# Wheel_speed_tester_rev1.net
KiCad netlist of a schematic drawn in EAGLE
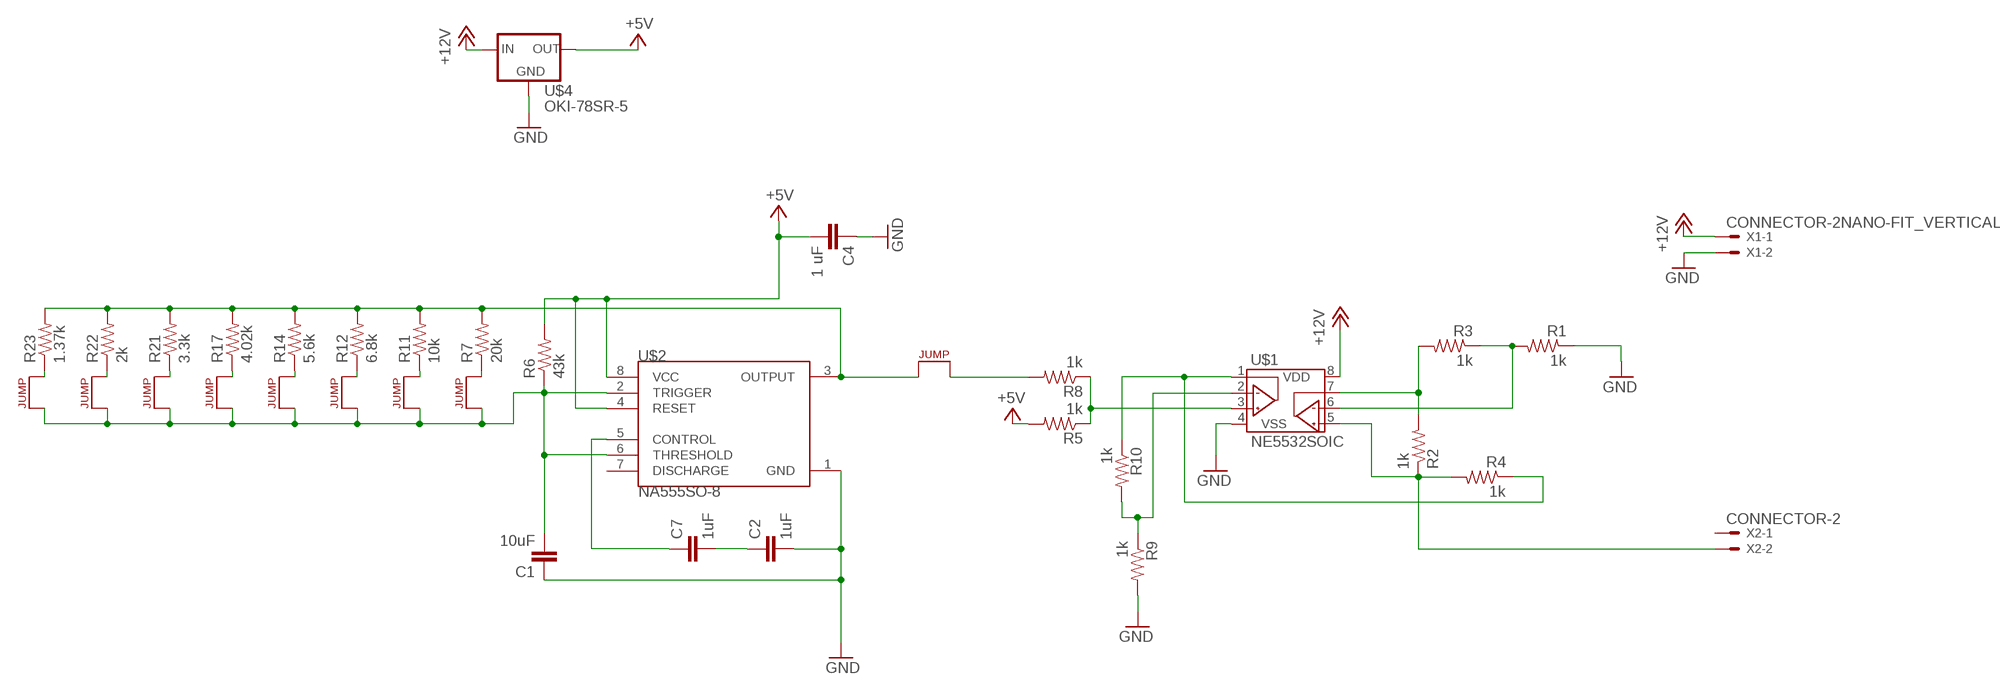
[diagram p0: schematic, sheet 1, part 1 of 2]
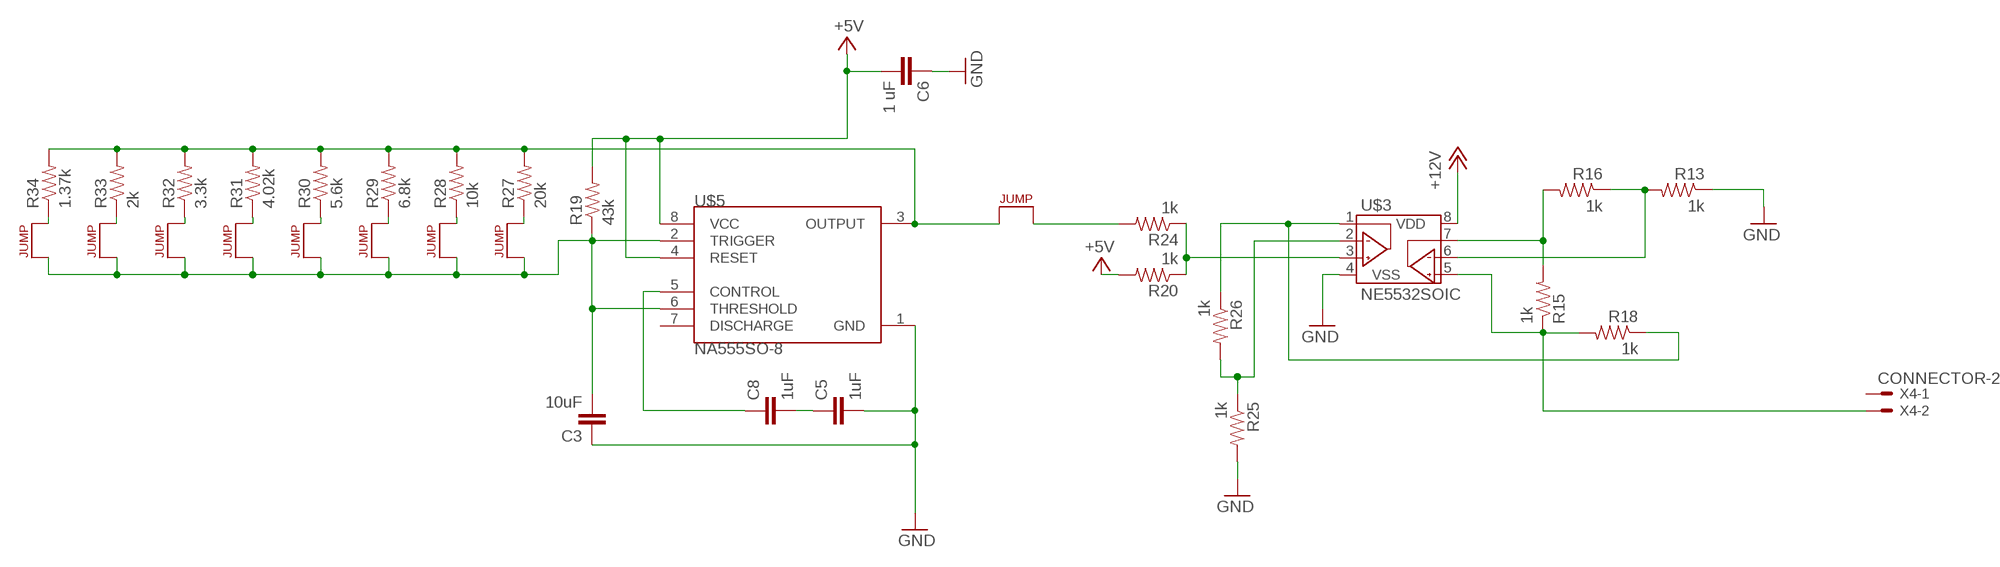
[diagram p1: schematic, sheet 1, part 2 of 2]

(export (version "E")
  (design (tool "Eeschema 10.0.6"))
  (components
    (comp (ref "C1")
      (value "10uF")
      (footprint "eagle-import:0603-CAP")
      (libsource (lib "eagle-import") (part "CAP0603-CAP"))
    )
    (comp (ref "C2")
      (value "1uF")
      (footprint "eagle-import:0603-CAP")
      (libsource (lib "eagle-import") (part "CAP0603-CAP"))
    )
    (comp (ref "C3")
      (value "10uF")
      (footprint "eagle-import:0603-CAP")
      (libsource (lib "eagle-import") (part "CAP0603-CAP"))
    )
    (comp (ref "C4")
      (value "1 uF")
      (footprint "eagle-import:0603-CAP")
      (libsource (lib "eagle-import") (part "CAP0603-CAP"))
    )
    (comp (ref "C5")
      (value "1uF")
      (footprint "eagle-import:0603-CAP")
      (libsource (lib "eagle-import") (part "CAP0603-CAP"))
    )
    (comp (ref "C6")
      (value "1 uF")
      (footprint "eagle-import:0603-CAP")
      (libsource (lib "eagle-import") (part "CAP0603-CAP"))
    )
    (comp (ref "C7")
      (value "1uF")
      (footprint "eagle-import:0603-CAP")
      (libsource (lib "eagle-import") (part "CAP0603-CAP"))
    )
    (comp (ref "C8")
      (value "1uF")
      (footprint "eagle-import:0603-CAP")
      (libsource (lib "eagle-import") (part "CAP0603-CAP"))
    )
    (comp (ref "J1")
      (value "JUMPER.1")
      (footprint "eagle-import:1X02")
      (libsource (lib "eagle-import") (part "JUMPER.1"))
    )
    (comp (ref "J2")
      (value "JUMPER.1")
      (footprint "eagle-import:1X02")
      (libsource (lib "eagle-import") (part "JUMPER.1"))
    )
    (comp (ref "J3")
      (value "JUMPER.1")
      (footprint "eagle-import:1X02")
      (libsource (lib "eagle-import") (part "JUMPER.1"))
    )
    (comp (ref "J4")
      (value "JUMPER.1")
      (footprint "eagle-import:1X02")
      (libsource (lib "eagle-import") (part "JUMPER.1"))
    )
    (comp (ref "J5")
      (value "JUMPER.1")
      (footprint "eagle-import:1X02")
      (libsource (lib "eagle-import") (part "JUMPER.1"))
    )
    (comp (ref "J6")
      (value "JUMPER.1")
      (footprint "eagle-import:1X02")
      (libsource (lib "eagle-import") (part "JUMPER.1"))
    )
    (comp (ref "J7")
      (value "JUMPER.1")
      (footprint "eagle-import:1X02")
      (libsource (lib "eagle-import") (part "JUMPER.1"))
    )
    (comp (ref "J8")
      (value "JUMPER.1")
      (footprint "eagle-import:1X02")
      (libsource (lib "eagle-import") (part "JUMPER.1"))
    )
    (comp (ref "J9")
      (value "JUMPER.1")
      (footprint "eagle-import:1X02")
      (libsource (lib "eagle-import") (part "JUMPER.1"))
    )
    (comp (ref "J10")
      (value "JUMPER.1")
      (footprint "eagle-import:1X02")
      (libsource (lib "eagle-import") (part "JUMPER.1"))
    )
    (comp (ref "J11")
      (value "JUMPER.1")
      (footprint "eagle-import:1X02")
      (libsource (lib "eagle-import") (part "JUMPER.1"))
    )
    (comp (ref "J12")
      (value "JUMPER.1")
      (footprint "eagle-import:1X02")
      (libsource (lib "eagle-import") (part "JUMPER.1"))
    )
    (comp (ref "J13")
      (value "JUMPER.1")
      (footprint "eagle-import:1X02")
      (libsource (lib "eagle-import") (part "JUMPER.1"))
    )
    (comp (ref "J14")
      (value "JUMPER.1")
      (footprint "eagle-import:1X02")
      (libsource (lib "eagle-import") (part "JUMPER.1"))
    )
    (comp (ref "J15")
      (value "JUMPER.1")
      (footprint "eagle-import:1X02")
      (libsource (lib "eagle-import") (part "JUMPER.1"))
    )
    (comp (ref "J16")
      (value "JUMPER.1")
      (footprint "eagle-import:1X02")
      (libsource (lib "eagle-import") (part "JUMPER.1"))
    )
    (comp (ref "J17")
      (value "JUMPER.1")
      (footprint "eagle-import:1X02")
      (libsource (lib "eagle-import") (part "JUMPER.1"))
    )
    (comp (ref "J18")
      (value "JUMPER.1")
      (footprint "eagle-import:1X02")
      (libsource (lib "eagle-import") (part "JUMPER.1"))
    )
    (comp (ref "R1")
      (value "1k")
      (footprint "eagle-import:0603-RES")
      (libsource (lib "eagle-import") (part "RESISTOR0603"))
    )
    (comp (ref "R2")
      (value "1k")
      (footprint "eagle-import:0603-RES")
      (libsource (lib "eagle-import") (part "RESISTOR0603"))
    )
    (comp (ref "R3")
      (value "1k")
      (footprint "eagle-import:0603-RES")
      (libsource (lib "eagle-import") (part "RESISTOR0603"))
    )
    (comp (ref "R4")
      (value "1k")
      (footprint "eagle-import:0603-RES")
      (libsource (lib "eagle-import") (part "RESISTOR0603"))
    )
    (comp (ref "R5")
      (value "1k")
      (footprint "eagle-import:0603-RES")
      (libsource (lib "eagle-import") (part "RESISTOR0603"))
    )
    (comp (ref "R6")
      (value "43k")
      (footprint "eagle-import:0603-RES")
      (libsource (lib "eagle-import") (part "RESISTOR0603"))
    )
    (comp (ref "R7")
      (value "20k")
      (footprint "eagle-import:0603-RES")
      (libsource (lib "eagle-import") (part "RESISTOR0603"))
    )
    (comp (ref "R8")
      (value "1k")
      (footprint "eagle-import:0603-RES")
      (libsource (lib "eagle-import") (part "RESISTOR0603"))
    )
    (comp (ref "R9")
      (value "1k")
      (footprint "eagle-import:0603-RES")
      (libsource (lib "eagle-import") (part "RESISTOR0603"))
    )
    (comp (ref "R10")
      (value "1k")
      (footprint "eagle-import:0603-RES")
      (libsource (lib "eagle-import") (part "RESISTOR0603"))
    )
    (comp (ref "R11")
      (value "10k")
      (footprint "eagle-import:0603-RES")
      (libsource (lib "eagle-import") (part "RESISTOR0603"))
    )
    (comp (ref "R12")
      (value "6.8k")
      (footprint "eagle-import:0603-RES")
      (libsource (lib "eagle-import") (part "RESISTOR0603"))
    )
    (comp (ref "R13")
      (value "1k")
      (footprint "eagle-import:0603-RES")
      (libsource (lib "eagle-import") (part "RESISTOR0603"))
    )
    (comp (ref "R14")
      (value "5.6k")
      (footprint "eagle-import:0603-RES")
      (libsource (lib "eagle-import") (part "RESISTOR0603"))
    )
    (comp (ref "R15")
      (value "1k")
      (footprint "eagle-import:0603-RES")
      (libsource (lib "eagle-import") (part "RESISTOR0603"))
    )
    (comp (ref "R16")
      (value "1k")
      (footprint "eagle-import:0603-RES")
      (libsource (lib "eagle-import") (part "RESISTOR0603"))
    )
    (comp (ref "R17")
      (value "4.02k")
      (footprint "eagle-import:0603-RES")
      (libsource (lib "eagle-import") (part "RESISTOR0603"))
    )
    (comp (ref "R18")
      (value "1k")
      (footprint "eagle-import:0603-RES")
      (libsource (lib "eagle-import") (part "RESISTOR0603"))
    )
    (comp (ref "R19")
      (value "43k")
      (footprint "eagle-import:0603-RES")
      (libsource (lib "eagle-import") (part "RESISTOR0603"))
    )
    (comp (ref "R20")
      (value "1k")
      (footprint "eagle-import:0603-RES")
      (libsource (lib "eagle-import") (part "RESISTOR0603"))
    )
    (comp (ref "R21")
      (value "3.3k")
      (footprint "eagle-import:0603-RES")
      (libsource (lib "eagle-import") (part "RESISTOR0603"))
    )
    (comp (ref "R22")
      (value "2k")
      (footprint "eagle-import:0603-RES")
      (libsource (lib "eagle-import") (part "RESISTOR0603"))
    )
    (comp (ref "R23")
      (value "1.37k")
      (footprint "eagle-import:0603-RES")
      (libsource (lib "eagle-import") (part "RESISTOR0603"))
    )
    (comp (ref "R24")
      (value "1k")
      (footprint "eagle-import:0603-RES")
      (libsource (lib "eagle-import") (part "RESISTOR0603"))
    )
    (comp (ref "R25")
      (value "1k")
      (footprint "eagle-import:0603-RES")
      (libsource (lib "eagle-import") (part "RESISTOR0603"))
    )
    (comp (ref "R26")
      (value "1k")
      (footprint "eagle-import:0603-RES")
      (libsource (lib "eagle-import") (part "RESISTOR0603"))
    )
    (comp (ref "R27")
      (value "20k")
      (footprint "eagle-import:0603-RES")
      (libsource (lib "eagle-import") (part "RESISTOR0603"))
    )
    (comp (ref "R28")
      (value "10k")
      (footprint "eagle-import:0603-RES")
      (libsource (lib "eagle-import") (part "RESISTOR0603"))
    )
    (comp (ref "R29")
      (value "6.8k")
      (footprint "eagle-import:0603-RES")
      (libsource (lib "eagle-import") (part "RESISTOR0603"))
    )
    (comp (ref "R30")
      (value "5.6k")
      (footprint "eagle-import:0603-RES")
      (libsource (lib "eagle-import") (part "RESISTOR0603"))
    )
    (comp (ref "R31")
      (value "4.02k")
      (footprint "eagle-import:0603-RES")
      (libsource (lib "eagle-import") (part "RESISTOR0603"))
    )
    (comp (ref "R32")
      (value "3.3k")
      (footprint "eagle-import:0603-RES")
      (libsource (lib "eagle-import") (part "RESISTOR0603"))
    )
    (comp (ref "R33")
      (value "2k")
      (footprint "eagle-import:0603-RES")
      (libsource (lib "eagle-import") (part "RESISTOR0603"))
    )
    (comp (ref "R34")
      (value "1.37k")
      (footprint "eagle-import:0603-RES")
      (libsource (lib "eagle-import") (part "RESISTOR0603"))
    )
    (comp (ref "U$1")
      (value "NE5532SOIC")
      (footprint "eagle-import:SOIC-08")
      (libsource (lib "eagle-import") (part "NE5532SOIC"))
    )
    (comp (ref "U$2")
      (value "NA555SO-8")
      (footprint "eagle-import:SOIC-08")
      (libsource (lib "eagle-import") (part "NA555SO-8"))
    )
    (comp (ref "U$3")
      (value "NE5532SOIC")
      (footprint "eagle-import:SOIC-08")
      (libsource (lib "eagle-import") (part "NE5532SOIC"))
    )
    (comp (ref "U$4")
      (value "OKI-78SR-5")
      (footprint "eagle-import:OKI-78SR")
      (libsource (lib "eagle-import") (part "OKI-78SR-5"))
    )
    (comp (ref "U$5")
      (value "NA555SO-8")
      (footprint "eagle-import:SOIC-08")
      (libsource (lib "eagle-import") (part "NA555SO-8"))
    )
    (comp (ref "X1")
      (value "CONNECTOR-2NANO-FIT_VERTICAL-2")
      (footprint "eagle-import:NANO-FIT_VERTICAL-2")
      (libsource (lib "eagle-import") (part "CONNECTOR-2NANO-FIT_VERTICAL-2"))
    )
    (comp (ref "X2")
      (value "CONNECTOR-2")
      (footprint "eagle-import:MINIFIT_5566-2")
      (libsource (lib "eagle-import") (part "CONNECTOR-2"))
    )
    (comp (ref "X4")
      (value "CONNECTOR-2")
      (footprint "eagle-import:MINIFIT_5566-2")
      (libsource (lib "eagle-import") (part "CONNECTOR-2"))
    )
  )
  (nets
    (net (code "1") (name "+5V") (class "Default")
      (node (ref "C4") (pin "2") (pinfunction "2_2") (pintype "passive"))
      (node (ref "C6") (pin "2") (pinfunction "2_2") (pintype "passive"))
      (node (ref "R19") (pin "2") (pinfunction "2_2") (pintype "passive"))
      (node (ref "R20") (pin "2") (pinfunction "2_2") (pintype "passive"))
      (node (ref "R5") (pin "2") (pinfunction "2_2") (pintype "passive"))
      (node (ref "R6") (pin "2") (pinfunction "2_2") (pintype "passive"))
      (node (ref "U$2") (pin "4") (pinfunction "RESET_4") (pintype "passive"))
      (node (ref "U$2") (pin "8") (pinfunction "VCC_8") (pintype "passive"))
      (node (ref "U$4") (pin "3") (pinfunction "OUT_3") (pintype "output"))
      (node (ref "U$5") (pin "4") (pinfunction "RESET_4") (pintype "passive"))
      (node (ref "U$5") (pin "8") (pinfunction "VCC_8") (pintype "passive"))
    )
    (net (code "2") (name "+12V") (class "Default")
      (node (ref "U$1") (pin "8") (pinfunction "VDD_8") (pintype "passive"))
      (node (ref "U$3") (pin "8") (pinfunction "VDD_8") (pintype "passive"))
      (node (ref "U$4") (pin "1") (pinfunction "IN_1") (pintype "input"))
      (node (ref "X1") (pin "P$1") (pinfunction "S_P$1") (pintype "passive"))
    )
    (net (code "3") (name "GND") (class "Default")
      (node (ref "C1") (pin "1") (pinfunction "1_1") (pintype "passive"))
      (node (ref "C2") (pin "2") (pinfunction "2_2") (pintype "passive"))
      (node (ref "C3") (pin "1") (pinfunction "1_1") (pintype "passive"))
      (node (ref "C4") (pin "1") (pinfunction "1_1") (pintype "passive"))
      (node (ref "C5") (pin "2") (pinfunction "2_2") (pintype "passive"))
      (node (ref "C6") (pin "1") (pinfunction "1_1") (pintype "passive"))
      (node (ref "R1") (pin "1") (pinfunction "1_1") (pintype "passive"))
      (node (ref "R13") (pin "1") (pinfunction "1_1") (pintype "passive"))
      (node (ref "R25") (pin "2") (pinfunction "2_2") (pintype "passive"))
      (node (ref "R9") (pin "2") (pinfunction "2_2") (pintype "passive"))
      (node (ref "U$1") (pin "4") (pinfunction "VSS_4") (pintype "passive"))
      (node (ref "U$2") (pin "1") (pinfunction "GND_1") (pintype "passive"))
      (node (ref "U$3") (pin "4") (pinfunction "VSS_4") (pintype "passive"))
      (node (ref "U$4") (pin "2") (pinfunction "GND_2") (pintype "input"))
      (node (ref "U$5") (pin "1") (pinfunction "GND_1") (pintype "passive"))
      (node (ref "X1") (pin "P$2") (pinfunction "S_P$2") (pintype "passive"))
    )
    (net (code "4") (name "Net-(C2-Pad1)") (class "Default")
      (node (ref "C2") (pin "1") (pinfunction "1_1") (pintype "passive"))
      (node (ref "C7") (pin "2") (pinfunction "2_2") (pintype "passive"))
    )
    (net (code "5") (name "Net-(C5-Pad1)") (class "Default")
      (node (ref "C5") (pin "1") (pinfunction "1_1") (pintype "passive"))
      (node (ref "C8") (pin "2") (pinfunction "2_2") (pintype "passive"))
    )
    (net (code "6") (name "Net-(J1-P$1)") (class "Default")
      (node (ref "C1") (pin "2") (pinfunction "2_2") (pintype "passive"))
      (node (ref "J1") (pin "1") (pinfunction "P$1_1") (pintype "bidirectional"))
      (node (ref "J3") (pin "1") (pinfunction "P$1_1") (pintype "bidirectional"))
      (node (ref "J4") (pin "1") (pinfunction "P$1_1") (pintype "bidirectional"))
      (node (ref "J5") (pin "1") (pinfunction "P$1_1") (pintype "bidirectional"))
      (node (ref "J6") (pin "1") (pinfunction "P$1_1") (pintype "bidirectional"))
      (node (ref "J7") (pin "1") (pinfunction "P$1_1") (pintype "bidirectional"))
      (node (ref "J8") (pin "1") (pinfunction "P$1_1") (pintype "bidirectional"))
      (node (ref "J9") (pin "1") (pinfunction "P$1_1") (pintype "bidirectional"))
      (node (ref "R6") (pin "1") (pinfunction "1_1") (pintype "passive"))
      (node (ref "U$2") (pin "2") (pinfunction "TRIGGER_2") (pintype "passive"))
      (node (ref "U$2") (pin "6") (pinfunction "THRESHOLD_6") (pintype "passive"))
    )
    (net (code "7") (name "Net-(J1-P$2)") (class "Default")
      (node (ref "J1") (pin "2") (pinfunction "P$2_2") (pintype "bidirectional"))
      (node (ref "R23") (pin "1") (pinfunction "1_1") (pintype "passive"))
    )
    (net (code "8") (name "Net-(J2-P$1)") (class "Default")
      (node (ref "J2") (pin "1") (pinfunction "P$1_1") (pintype "bidirectional"))
      (node (ref "R11") (pin "2") (pinfunction "2_2") (pintype "passive"))
      (node (ref "R12") (pin "2") (pinfunction "2_2") (pintype "passive"))
      (node (ref "R14") (pin "2") (pinfunction "2_2") (pintype "passive"))
      (node (ref "R17") (pin "2") (pinfunction "2_2") (pintype "passive"))
      (node (ref "R21") (pin "2") (pinfunction "2_2") (pintype "passive"))
      (node (ref "R22") (pin "2") (pinfunction "2_2") (pintype "passive"))
      (node (ref "R23") (pin "2") (pinfunction "2_2") (pintype "passive"))
      (node (ref "R7") (pin "2") (pinfunction "2_2") (pintype "passive"))
      (node (ref "U$2") (pin "3") (pinfunction "OUTPUT_3") (pintype "passive"))
    )
    (net (code "9") (name "Net-(J2-P$2)") (class "Default")
      (node (ref "J2") (pin "2") (pinfunction "P$2_2") (pintype "bidirectional"))
      (node (ref "R8") (pin "2") (pinfunction "2_2") (pintype "passive"))
    )
    (net (code "10") (name "Net-(J3-P$2)") (class "Default")
      (node (ref "J3") (pin "2") (pinfunction "P$2_2") (pintype "bidirectional"))
      (node (ref "R22") (pin "1") (pinfunction "1_1") (pintype "passive"))
    )
    (net (code "11") (name "Net-(J4-P$2)") (class "Default")
      (node (ref "J4") (pin "2") (pinfunction "P$2_2") (pintype "bidirectional"))
      (node (ref "R21") (pin "1") (pinfunction "1_1") (pintype "passive"))
    )
    (net (code "12") (name "Net-(J5-P$2)") (class "Default")
      (node (ref "J5") (pin "2") (pinfunction "P$2_2") (pintype "bidirectional"))
      (node (ref "R17") (pin "1") (pinfunction "1_1") (pintype "passive"))
    )
    (net (code "13") (name "Net-(J6-P$2)") (class "Default")
      (node (ref "J6") (pin "2") (pinfunction "P$2_2") (pintype "bidirectional"))
      (node (ref "R14") (pin "1") (pinfunction "1_1") (pintype "passive"))
    )
    (net (code "14") (name "Net-(J7-P$2)") (class "Default")
      (node (ref "J7") (pin "2") (pinfunction "P$2_2") (pintype "bidirectional"))
      (node (ref "R12") (pin "1") (pinfunction "1_1") (pintype "passive"))
    )
    (net (code "15") (name "Net-(J8-P$2)") (class "Default")
      (node (ref "J8") (pin "2") (pinfunction "P$2_2") (pintype "bidirectional"))
      (node (ref "R11") (pin "1") (pinfunction "1_1") (pintype "passive"))
    )
    (net (code "16") (name "Net-(J9-P$2)") (class "Default")
      (node (ref "J9") (pin "2") (pinfunction "P$2_2") (pintype "bidirectional"))
      (node (ref "R7") (pin "1") (pinfunction "1_1") (pintype "passive"))
    )
    (net (code "17") (name "Net-(J10-P$1)") (class "Default")
      (node (ref "J10") (pin "1") (pinfunction "P$1_1") (pintype "bidirectional"))
      (node (ref "R27") (pin "2") (pinfunction "2_2") (pintype "passive"))
      (node (ref "R28") (pin "2") (pinfunction "2_2") (pintype "passive"))
      (node (ref "R29") (pin "2") (pinfunction "2_2") (pintype "passive"))
      (node (ref "R30") (pin "2") (pinfunction "2_2") (pintype "passive"))
      (node (ref "R31") (pin "2") (pinfunction "2_2") (pintype "passive"))
      (node (ref "R32") (pin "2") (pinfunction "2_2") (pintype "passive"))
      (node (ref "R33") (pin "2") (pinfunction "2_2") (pintype "passive"))
      (node (ref "R34") (pin "2") (pinfunction "2_2") (pintype "passive"))
      (node (ref "U$5") (pin "3") (pinfunction "OUTPUT_3") (pintype "passive"))
    )
    (net (code "18") (name "Net-(J10-P$2)") (class "Default")
      (node (ref "J10") (pin "2") (pinfunction "P$2_2") (pintype "bidirectional"))
      (node (ref "R24") (pin "2") (pinfunction "2_2") (pintype "passive"))
    )
    (net (code "19") (name "Net-(J11-P$1)") (class "Default")
      (node (ref "C3") (pin "2") (pinfunction "2_2") (pintype "passive"))
      (node (ref "J11") (pin "1") (pinfunction "P$1_1") (pintype "bidirectional"))
      (node (ref "J12") (pin "1") (pinfunction "P$1_1") (pintype "bidirectional"))
      (node (ref "J13") (pin "1") (pinfunction "P$1_1") (pintype "bidirectional"))
      (node (ref "J14") (pin "1") (pinfunction "P$1_1") (pintype "bidirectional"))
      (node (ref "J15") (pin "1") (pinfunction "P$1_1") (pintype "bidirectional"))
      (node (ref "J16") (pin "1") (pinfunction "P$1_1") (pintype "bidirectional"))
      (node (ref "J17") (pin "1") (pinfunction "P$1_1") (pintype "bidirectional"))
      (node (ref "J18") (pin "1") (pinfunction "P$1_1") (pintype "bidirectional"))
      (node (ref "R19") (pin "1") (pinfunction "1_1") (pintype "passive"))
      (node (ref "U$5") (pin "2") (pinfunction "TRIGGER_2") (pintype "passive"))
      (node (ref "U$5") (pin "6") (pinfunction "THRESHOLD_6") (pintype "passive"))
    )
    (net (code "20") (name "Net-(J11-P$2)") (class "Default")
      (node (ref "J11") (pin "2") (pinfunction "P$2_2") (pintype "bidirectional"))
      (node (ref "R34") (pin "1") (pinfunction "1_1") (pintype "passive"))
    )
    (net (code "21") (name "Net-(J12-P$2)") (class "Default")
      (node (ref "J12") (pin "2") (pinfunction "P$2_2") (pintype "bidirectional"))
      (node (ref "R33") (pin "1") (pinfunction "1_1") (pintype "passive"))
    )
    (net (code "22") (name "Net-(J13-P$2)") (class "Default")
      (node (ref "J13") (pin "2") (pinfunction "P$2_2") (pintype "bidirectional"))
      (node (ref "R32") (pin "1") (pinfunction "1_1") (pintype "passive"))
    )
    (net (code "23") (name "Net-(J14-P$2)") (class "Default")
      (node (ref "J14") (pin "2") (pinfunction "P$2_2") (pintype "bidirectional"))
      (node (ref "R31") (pin "1") (pinfunction "1_1") (pintype "passive"))
    )
    (net (code "24") (name "Net-(J15-P$2)") (class "Default")
      (node (ref "J15") (pin "2") (pinfunction "P$2_2") (pintype "bidirectional"))
      (node (ref "R30") (pin "1") (pinfunction "1_1") (pintype "passive"))
    )
    (net (code "25") (name "Net-(J16-P$2)") (class "Default")
      (node (ref "J16") (pin "2") (pinfunction "P$2_2") (pintype "bidirectional"))
      (node (ref "R29") (pin "1") (pinfunction "1_1") (pintype "passive"))
    )
    (net (code "26") (name "Net-(J17-P$2)") (class "Default")
      (node (ref "J17") (pin "2") (pinfunction "P$2_2") (pintype "bidirectional"))
      (node (ref "R28") (pin "1") (pinfunction "1_1") (pintype "passive"))
    )
    (net (code "27") (name "Net-(J18-P$2)") (class "Default")
      (node (ref "J18") (pin "2") (pinfunction "P$2_2") (pintype "bidirectional"))
      (node (ref "R27") (pin "1") (pinfunction "1_1") (pintype "passive"))
    )
    (net (code "28") (name "Net-(U$1-VINA+)") (class "Default")
      (node (ref "R5") (pin "1") (pinfunction "1_1") (pintype "passive"))
      (node (ref "R8") (pin "1") (pinfunction "1_1") (pintype "passive"))
      (node (ref "U$1") (pin "3") (pinfunction "VINA+_3") (pintype "passive"))
    )
    (net (code "29") (name "Net-(U$1-VINA-)") (class "Default")
      (node (ref "R10") (pin "2") (pinfunction "2_2") (pintype "passive"))
      (node (ref "R9") (pin "1") (pinfunction "1_1") (pintype "passive"))
      (node (ref "U$1") (pin "2") (pinfunction "VINA-_2") (pintype "passive"))
    )
    (net (code "30") (name "Net-(U$1-VINB+)") (class "Default")
      (node (ref "R2") (pin "1") (pinfunction "1_1") (pintype "passive"))
      (node (ref "R4") (pin "2") (pinfunction "2_2") (pintype "passive"))
      (node (ref "U$1") (pin "5") (pinfunction "VINB+_5") (pintype "passive"))
      (node (ref "X2") (pin "2") (pinfunction "S_2") (pintype "passive"))
    )
    (net (code "31") (name "Net-(U$1-VINB-)") (class "Default")
      (node (ref "R1") (pin "2") (pinfunction "2_2") (pintype "passive"))
      (node (ref "R3") (pin "1") (pinfunction "1_1") (pintype "passive"))
      (node (ref "U$1") (pin "6") (pinfunction "VINB-_6") (pintype "passive"))
    )
    (net (code "32") (name "Net-(U$1-VOUTA)") (class "Default")
      (node (ref "R10") (pin "1") (pinfunction "1_1") (pintype "passive"))
      (node (ref "R4") (pin "1") (pinfunction "1_1") (pintype "passive"))
      (node (ref "U$1") (pin "1") (pinfunction "VOUTA_1") (pintype "passive"))
    )
    (net (code "33") (name "Net-(U$1-VOUTB)") (class "Default")
      (node (ref "R2") (pin "2") (pinfunction "2_2") (pintype "passive"))
      (node (ref "R3") (pin "2") (pinfunction "2_2") (pintype "passive"))
      (node (ref "U$1") (pin "7") (pinfunction "VOUTB_7") (pintype "passive"))
    )
    (net (code "34") (name "Net-(U$2-CONTROL)") (class "Default")
      (node (ref "C7") (pin "1") (pinfunction "1_1") (pintype "passive"))
      (node (ref "U$2") (pin "5") (pinfunction "CONTROL_5") (pintype "passive"))
    )
    (net (code "35") (name "Net-(U$3-VINA+)") (class "Default")
      (node (ref "R20") (pin "1") (pinfunction "1_1") (pintype "passive"))
      (node (ref "R24") (pin "1") (pinfunction "1_1") (pintype "passive"))
      (node (ref "U$3") (pin "3") (pinfunction "VINA+_3") (pintype "passive"))
    )
    (net (code "36") (name "Net-(U$3-VINA-)") (class "Default")
      (node (ref "R25") (pin "1") (pinfunction "1_1") (pintype "passive"))
      (node (ref "R26") (pin "2") (pinfunction "2_2") (pintype "passive"))
      (node (ref "U$3") (pin "2") (pinfunction "VINA-_2") (pintype "passive"))
    )
    (net (code "37") (name "Net-(U$3-VINB+)") (class "Default")
      (node (ref "R15") (pin "1") (pinfunction "1_1") (pintype "passive"))
      (node (ref "R18") (pin "2") (pinfunction "2_2") (pintype "passive"))
      (node (ref "U$3") (pin "5") (pinfunction "VINB+_5") (pintype "passive"))
      (node (ref "X4") (pin "2") (pinfunction "S_2") (pintype "passive"))
    )
    (net (code "38") (name "Net-(U$3-VINB-)") (class "Default")
      (node (ref "R13") (pin "2") (pinfunction "2_2") (pintype "passive"))
      (node (ref "R16") (pin "1") (pinfunction "1_1") (pintype "passive"))
      (node (ref "U$3") (pin "6") (pinfunction "VINB-_6") (pintype "passive"))
    )
    (net (code "39") (name "Net-(U$3-VOUTA)") (class "Default")
      (node (ref "R18") (pin "1") (pinfunction "1_1") (pintype "passive"))
      (node (ref "R26") (pin "1") (pinfunction "1_1") (pintype "passive"))
      (node (ref "U$3") (pin "1") (pinfunction "VOUTA_1") (pintype "passive"))
    )
    (net (code "40") (name "Net-(U$3-VOUTB)") (class "Default")
      (node (ref "R15") (pin "2") (pinfunction "2_2") (pintype "passive"))
      (node (ref "R16") (pin "2") (pinfunction "2_2") (pintype "passive"))
      (node (ref "U$3") (pin "7") (pinfunction "VOUTB_7") (pintype "passive"))
    )
    (net (code "41") (name "Net-(U$5-CONTROL)") (class "Default")
      (node (ref "C8") (pin "1") (pinfunction "1_1") (pintype "passive"))
      (node (ref "U$5") (pin "5") (pinfunction "CONTROL_5") (pintype "passive"))
    )
    (net (code "42") (name "unconnected-(U$2-DISCHARGE-Pad7)") (class "Default")
      (node (ref "U$2") (pin "7") (pinfunction "DISCHARGE_7") (pintype "passive"))
    )
    (net (code "43") (name "unconnected-(U$5-DISCHARGE-Pad7)") (class "Default")
      (node (ref "U$5") (pin "7") (pinfunction "DISCHARGE_7") (pintype "passive"))
    )
    (net (code "44") (name "unconnected-(X2A-S-Pad1)") (class "Default")
      (node (ref "X2") (pin "1") (pinfunction "S_1") (pintype "passive"))
    )
    (net (code "45") (name "unconnected-(X4A-S-Pad1)") (class "Default")
      (node (ref "X4") (pin "1") (pinfunction "S_1") (pintype "passive"))
    )
  )
)
